# 119_02v2_INTELLIGENT_SENSOR_BOARD.net
KiCad netlist of a schematic drawn in EAGLE
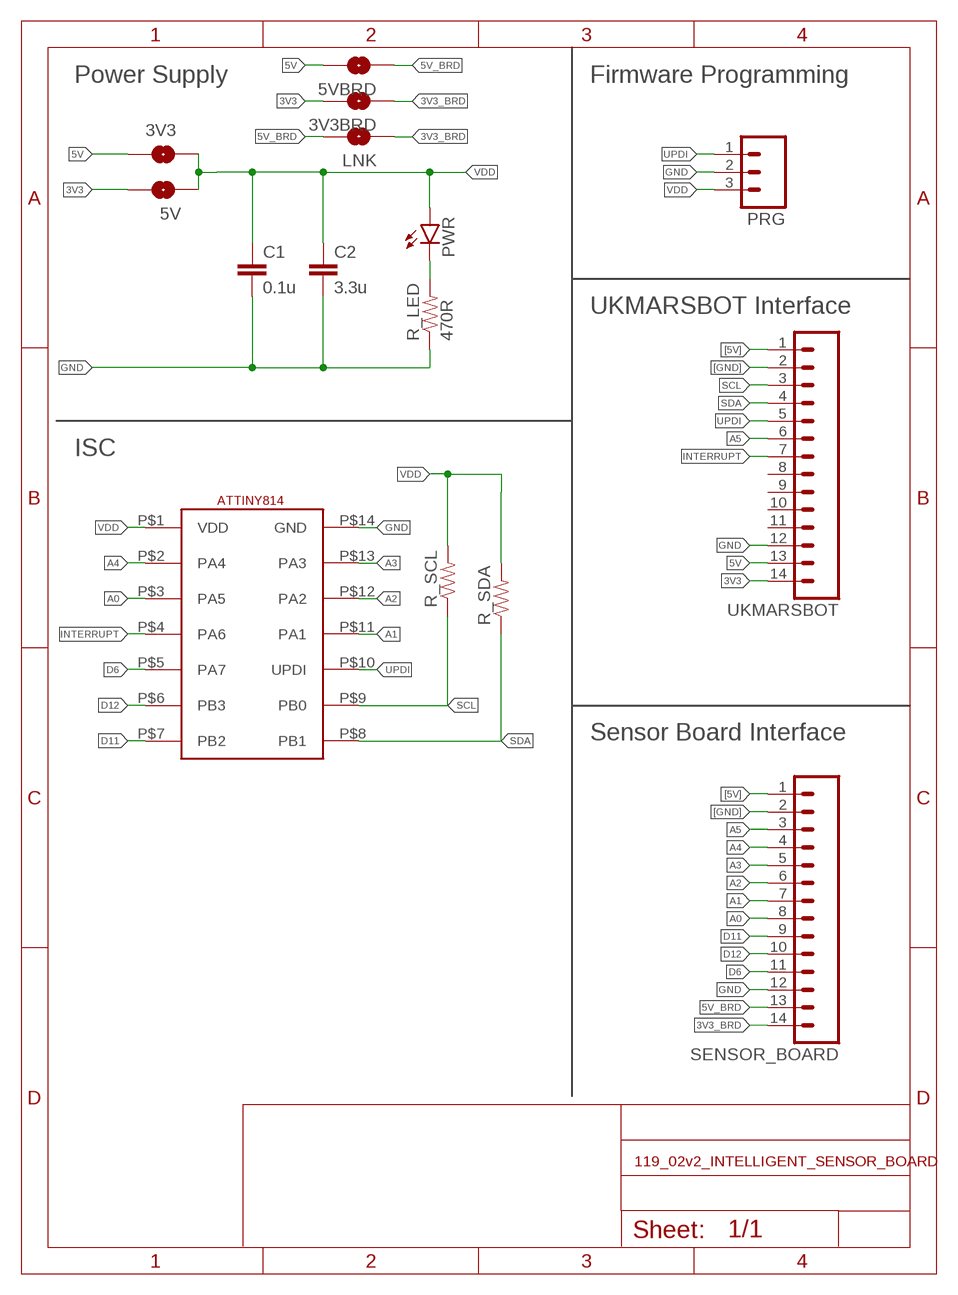
[diagram p0: schematic, sheet 1]

(export (version "E")
  (design (tool "Eeschema 10.0.6"))
  (components
    (comp (ref "3V3")
      (value "JUMPER-SMT_2_NO_SILK")
      (footprint "eagle-import:SMT-JUMPER_2_NO_SILK")
      (libsource (lib "eagle-import") (part "JUMPER-SMT_2_NO_SILK"))
    )
    (comp (ref "3V3BRD")
      (value "JUMPER-SMT_2_NO_SILK")
      (footprint "eagle-import:SMT-JUMPER_2_NO_SILK")
      (libsource (lib "eagle-import") (part "JUMPER-SMT_2_NO_SILK"))
    )
    (comp (ref "5V")
      (value "JUMPER-SMT_2_NO_SILK")
      (footprint "eagle-import:SMT-JUMPER_2_NO_SILK")
      (libsource (lib "eagle-import") (part "JUMPER-SMT_2_NO_SILK"))
    )
    (comp (ref "5VBRD")
      (value "JUMPER-SMT_2_NO_SILK")
      (footprint "eagle-import:SMT-JUMPER_2_NO_SILK")
      (libsource (lib "eagle-import") (part "JUMPER-SMT_2_NO_SILK"))
    )
    (comp (ref "C1")
      (value "0.1u")
      (footprint "eagle-import:0805")
      (libsource (lib "eagle-import") (part "CAP0805"))
    )
    (comp (ref "C2")
      (value "3.3u")
      (footprint "eagle-import:0805")
      (libsource (lib "eagle-import") (part "CAP0805"))
    )
    (comp (ref "LNK")
      (value "JUMPER-SMT_2_NO_SILK")
      (footprint "eagle-import:SMT-JUMPER_2_NO_SILK")
      (libsource (lib "eagle-import") (part "JUMPER-SMT_2_NO_SILK"))
    )
    (comp (ref "PRG")
      (value "M03PTH")
      (footprint "eagle-import:1X03")
      (libsource (lib "eagle-import") (part "M03PTH"))
    )
    (comp (ref "PWR")
      (value "LEDCHIP-LED0805")
      (footprint "eagle-import:CHIP-LED0805")
      (libsource (lib "eagle-import") (part "LEDCHIP-LED0805"))
    )
    (comp (ref "R_LED")
      (value "470R")
      (footprint "eagle-import:0805")
      (libsource (lib "eagle-import") (part "RESISTOR0805-RES"))
    )
    (comp (ref "R_SCL")
      (value "RESISTOR0805-RES")
      (footprint "eagle-import:0805")
      (libsource (lib "eagle-import") (part "RESISTOR0805-RES"))
    )
    (comp (ref "R_SDA")
      (value "RESISTOR0805-RES")
      (footprint "eagle-import:0805")
      (libsource (lib "eagle-import") (part "RESISTOR0805-RES"))
    )
    (comp (ref "SENSOR_BOARD")
      (value "M14")
      (footprint "eagle-import:1X14")
      (libsource (lib "eagle-import") (part "M14"))
    )
    (comp (ref "U$1")
      (value "ATTINY814")
      (footprint "eagle-import:ATTINY814")
      (libsource (lib "eagle-import") (part "ATTINY814"))
    )
    (comp (ref "UKMARSBOT")
      (value "M14")
      (footprint "eagle-import:1X14")
      (libsource (lib "eagle-import") (part "M14"))
    )
  )
  (nets
    (net (code "1") (name "3V3") (class "Default")
      (node (ref "3V3BRD") (pin "2") (pinfunction "2_2") (pintype "passive"))
      (node (ref "5V") (pin "2") (pinfunction "2_2") (pintype "passive"))
      (node (ref "UKMARSBOT") (pin "14") (pinfunction "14_14") (pintype "passive"))
    )
    (net (code "2") (name "3V3_BRD") (class "Default")
      (node (ref "3V3BRD") (pin "1") (pinfunction "1_1") (pintype "passive"))
      (node (ref "LNK") (pin "1") (pinfunction "1_1") (pintype "passive"))
      (node (ref "SENSOR_BOARD") (pin "14") (pinfunction "14_14") (pintype "passive"))
    )
    (net (code "3") (name "5V") (class "Default")
      (node (ref "3V3") (pin "2") (pinfunction "2_2") (pintype "passive"))
      (node (ref "5VBRD") (pin "2") (pinfunction "2_2") (pintype "passive"))
      (node (ref "UKMARSBOT") (pin "13") (pinfunction "13_13") (pintype "passive"))
    )
    (net (code "4") (name "5V_BRD") (class "Default")
      (node (ref "5VBRD") (pin "1") (pinfunction "1_1") (pintype "passive"))
      (node (ref "LNK") (pin "2") (pinfunction "2_2") (pintype "passive"))
      (node (ref "SENSOR_BOARD") (pin "13") (pinfunction "13_13") (pintype "passive"))
    )
    (net (code "5") (name "A0") (class "Default")
      (node (ref "SENSOR_BOARD") (pin "8") (pinfunction "8_8") (pintype "passive"))
      (node (ref "U$1") (pin "P$3") (pinfunction "PA5_P$3") (pintype "bidirectional"))
    )
    (net (code "6") (name "A1") (class "Default")
      (node (ref "SENSOR_BOARD") (pin "7") (pinfunction "7_7") (pintype "passive"))
      (node (ref "U$1") (pin "P$11") (pinfunction "PA1_P$11") (pintype "bidirectional"))
    )
    (net (code "7") (name "A2") (class "Default")
      (node (ref "SENSOR_BOARD") (pin "6") (pinfunction "6_6") (pintype "passive"))
      (node (ref "U$1") (pin "P$12") (pinfunction "PA2_P$12") (pintype "bidirectional"))
    )
    (net (code "8") (name "A3") (class "Default")
      (node (ref "SENSOR_BOARD") (pin "5") (pinfunction "5_5") (pintype "passive"))
      (node (ref "U$1") (pin "P$13") (pinfunction "PA3_P$13") (pintype "bidirectional"))
    )
    (net (code "9") (name "A4") (class "Default")
      (node (ref "SENSOR_BOARD") (pin "4") (pinfunction "4_4") (pintype "passive"))
      (node (ref "U$1") (pin "P$2") (pinfunction "PA4_P$2") (pintype "bidirectional"))
    )
    (net (code "10") (name "A5") (class "Default")
      (node (ref "SENSOR_BOARD") (pin "3") (pinfunction "3_3") (pintype "passive"))
      (node (ref "UKMARSBOT") (pin "6") (pinfunction "6_6") (pintype "passive"))
    )
    (net (code "11") (name "D6") (class "Default")
      (node (ref "SENSOR_BOARD") (pin "11") (pinfunction "11_11") (pintype "passive"))
      (node (ref "U$1") (pin "P$5") (pinfunction "PA7_P$5") (pintype "bidirectional"))
    )
    (net (code "12") (name "D11") (class "Default")
      (node (ref "SENSOR_BOARD") (pin "9") (pinfunction "9_9") (pintype "passive"))
      (node (ref "U$1") (pin "P$7") (pinfunction "PB2_P$7") (pintype "bidirectional"))
    )
    (net (code "13") (name "D12") (class "Default")
      (node (ref "SENSOR_BOARD") (pin "10") (pinfunction "10_10") (pintype "passive"))
      (node (ref "U$1") (pin "P$6") (pinfunction "PB3_P$6") (pintype "bidirectional"))
    )
    (net (code "14") (name "GND") (class "Default")
      (node (ref "C1") (pin "2") (pinfunction "2_2") (pintype "passive"))
      (node (ref "C2") (pin "2") (pinfunction "2_2") (pintype "passive"))
      (node (ref "PRG") (pin "2") (pinfunction "2_2") (pintype "passive"))
      (node (ref "R_LED") (pin "1") (pinfunction "1_1") (pintype "passive"))
      (node (ref "SENSOR_BOARD") (pin "12") (pinfunction "12_12") (pintype "passive"))
      (node (ref "U$1") (pin "P$14") (pinfunction "GND_P$14") (pintype "bidirectional"))
      (node (ref "UKMARSBOT") (pin "12") (pinfunction "12_12") (pintype "passive"))
    )
    (net (code "15") (name "INTERRUPT") (class "Default")
      (node (ref "U$1") (pin "P$4") (pinfunction "PA6_P$4") (pintype "bidirectional"))
      (node (ref "UKMARSBOT") (pin "7") (pinfunction "7_7") (pintype "passive"))
    )
    (net (code "16") (name "Net-(PWR-PadC)") (class "Default")
      (node (ref "PWR") (pin "C") (pinfunction "C_C") (pintype "passive"))
      (node (ref "R_LED") (pin "2") (pinfunction "2_2") (pintype "passive"))
    )
    (net (code "17") (name "SCL") (class "Default")
      (node (ref "R_SCL") (pin "1") (pinfunction "1_1") (pintype "passive"))
      (node (ref "U$1") (pin "P$9") (pinfunction "PB0_P$9") (pintype "bidirectional"))
      (node (ref "UKMARSBOT") (pin "3") (pinfunction "3_3") (pintype "passive"))
    )
    (net (code "18") (name "SDA") (class "Default")
      (node (ref "R_SDA") (pin "1") (pinfunction "1_1") (pintype "passive"))
      (node (ref "U$1") (pin "P$8") (pinfunction "PB1_P$8") (pintype "bidirectional"))
      (node (ref "UKMARSBOT") (pin "4") (pinfunction "4_4") (pintype "passive"))
    )
    (net (code "19") (name "UPDI") (class "Default")
      (node (ref "PRG") (pin "1") (pinfunction "1_1") (pintype "passive"))
      (node (ref "U$1") (pin "P$10") (pinfunction "UPDI_P$10") (pintype "bidirectional"))
      (node (ref "UKMARSBOT") (pin "5") (pinfunction "5_5") (pintype "passive"))
    )
    (net (code "20") (name "VDD") (class "Default")
      (node (ref "3V3") (pin "1") (pinfunction "1_1") (pintype "passive"))
      (node (ref "5V") (pin "1") (pinfunction "1_1") (pintype "passive"))
      (node (ref "C1") (pin "1") (pinfunction "1_1") (pintype "passive"))
      (node (ref "C2") (pin "1") (pinfunction "1_1") (pintype "passive"))
      (node (ref "PRG") (pin "3") (pinfunction "3_3") (pintype "passive"))
      (node (ref "PWR") (pin "A") (pinfunction "A_A") (pintype "passive"))
      (node (ref "R_SCL") (pin "2") (pinfunction "2_2") (pintype "passive"))
      (node (ref "R_SDA") (pin "2") (pinfunction "2_2") (pintype "passive"))
      (node (ref "U$1") (pin "P$1") (pinfunction "VDD_P$1") (pintype "bidirectional"))
    )
    (net (code "21") (name "[5V]") (class "Default")
      (node (ref "SENSOR_BOARD") (pin "1") (pinfunction "1_1") (pintype "passive"))
      (node (ref "UKMARSBOT") (pin "1") (pinfunction "1_1") (pintype "passive"))
    )
    (net (code "22") (name "[GND]") (class "Default")
      (node (ref "SENSOR_BOARD") (pin "2") (pinfunction "2_2") (pintype "passive"))
      (node (ref "UKMARSBOT") (pin "2") (pinfunction "2_2") (pintype "passive"))
    )
    (net (code "23") (name "unconnected-(UKMARSBOT-Pad8)") (class "Default")
      (node (ref "UKMARSBOT") (pin "8") (pinfunction "8_8") (pintype "passive"))
    )
    (net (code "24") (name "unconnected-(UKMARSBOT-Pad9)") (class "Default")
      (node (ref "UKMARSBOT") (pin "9") (pinfunction "9_9") (pintype "passive"))
    )
    (net (code "25") (name "unconnected-(UKMARSBOT-Pad10)") (class "Default")
      (node (ref "UKMARSBOT") (pin "10") (pinfunction "10_10") (pintype "passive"))
    )
    (net (code "26") (name "unconnected-(UKMARSBOT-Pad11)") (class "Default")
      (node (ref "UKMARSBOT") (pin "11") (pinfunction "11_11") (pintype "passive"))
    )
  )
)
